# LC_Agregation_Boards.net
KiCad netlist of a schematic drawn in Altium Designer
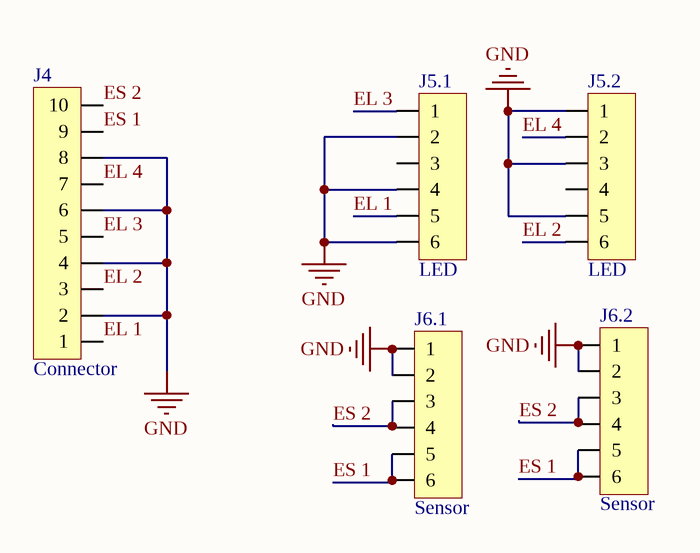
[diagram p0: LC Agregation Boards.SchDoc]

(export (version "E")
  (design (tool "Eeschema 10.0.6"))
  (components
    (comp (ref "J4")
      (value "Connector")
      (footprint "Connector:LINE 2.54 x 10D (2 x 5) - BH")
      (description "Vert, Dbl line, Male")
      (libsource (lib "Connector") (part "PLD-10 (2 x 5)"))
    )
    (comp (ref "J5.1")
      (value "LED")
      (footprint "Connector:LINE 2.54 x 6D (2 x 3)")
      (description "Vert, Dbl line, Male")
      (libsource (lib "Connector") (part "PLD-6 (2 x 3)"))
    )
    (comp (ref "J5.2")
      (value "LED")
      (footprint "Connector:LINE 2.54 x 6D (2 x 3)")
      (description "Vert, Dbl line, Male")
      (libsource (lib "Connector") (part "PLD-6 (2 x 3)"))
    )
    (comp (ref "J6.1")
      (value "Sensor")
      (footprint "Connector:LINE 2.54 x 6D (2 x 3)")
      (description "Vert, Dbl line, Male")
      (libsource (lib "Connector") (part "PLD-6 (2 x 3)"))
    )
    (comp (ref "J6.2")
      (value "Sensor")
      (footprint "Connector:LINE 2.54 x 6D (2 x 3)")
      (description "Vert, Dbl line, Male")
      (libsource (lib "Connector") (part "PLD-6 (2 x 3)"))
    )
  )
  (nets
    (net (code "1") (name "/EL 1") (class "Default")
      (node (ref "J4") (pin "1") (pinfunction "1_1") (pintype "passive"))
      (node (ref "J5.1") (pin "5") (pinfunction "5_5") (pintype "passive"))
    )
    (net (code "2") (name "/EL 2") (class "Default")
      (node (ref "J4") (pin "3") (pinfunction "3_3") (pintype "passive"))
      (node (ref "J5.2") (pin "6") (pinfunction "6_6") (pintype "passive"))
    )
    (net (code "3") (name "/EL 3") (class "Default")
      (node (ref "J4") (pin "5") (pinfunction "5_5") (pintype "passive"))
      (node (ref "J5.1") (pin "1") (pinfunction "1_1") (pintype "passive"))
    )
    (net (code "4") (name "/EL 4") (class "Default")
      (node (ref "J4") (pin "7") (pinfunction "7_7") (pintype "passive"))
      (node (ref "J5.2") (pin "2") (pinfunction "2_2") (pintype "passive"))
    )
    (net (code "5") (name "/ES 1") (class "Default")
      (node (ref "J4") (pin "9") (pinfunction "9_9") (pintype "passive"))
      (node (ref "J6.1") (pin "5") (pinfunction "5_5") (pintype "passive"))
      (node (ref "J6.1") (pin "6") (pinfunction "6_6") (pintype "passive"))
      (node (ref "J6.2") (pin "5") (pinfunction "5_5") (pintype "passive"))
      (node (ref "J6.2") (pin "6") (pinfunction "6_6") (pintype "passive"))
    )
    (net (code "6") (name "/ES 2") (class "Default")
      (node (ref "J4") (pin "10") (pinfunction "10_10") (pintype "passive"))
      (node (ref "J6.1") (pin "3") (pinfunction "3_3") (pintype "passive"))
      (node (ref "J6.1") (pin "4") (pinfunction "4_4") (pintype "passive"))
      (node (ref "J6.2") (pin "3") (pinfunction "3_3") (pintype "passive"))
      (node (ref "J6.2") (pin "4") (pinfunction "4_4") (pintype "passive"))
    )
    (net (code "7") (name "GND") (class "Default")
      (node (ref "J4") (pin "2") (pinfunction "2_2") (pintype "passive"))
      (node (ref "J4") (pin "4") (pinfunction "4_4") (pintype "passive"))
      (node (ref "J4") (pin "6") (pinfunction "6_6") (pintype "passive"))
      (node (ref "J4") (pin "8") (pinfunction "8_8") (pintype "passive"))
      (node (ref "J5.1") (pin "2") (pinfunction "2_2") (pintype "passive"))
      (node (ref "J5.1") (pin "4") (pinfunction "4_4") (pintype "passive"))
      (node (ref "J5.1") (pin "6") (pinfunction "6_6") (pintype "passive"))
      (node (ref "J5.2") (pin "1") (pinfunction "1_1") (pintype "passive"))
      (node (ref "J5.2") (pin "3") (pinfunction "3_3") (pintype "passive"))
      (node (ref "J5.2") (pin "5") (pinfunction "5_5") (pintype "passive"))
      (node (ref "J6.1") (pin "1") (pinfunction "1_1") (pintype "passive"))
      (node (ref "J6.1") (pin "2") (pinfunction "2_2") (pintype "passive"))
      (node (ref "J6.2") (pin "1") (pinfunction "1_1") (pintype "passive"))
      (node (ref "J6.2") (pin "2") (pinfunction "2_2") (pintype "passive"))
    )
    (net (code "8") (name "unconnected-(J5.1-Pad3)") (class "Default")
      (node (ref "J5.1") (pin "3") (pinfunction "3_3") (pintype "passive"))
    )
    (net (code "9") (name "unconnected-(J5.2-Pad4)") (class "Default")
      (node (ref "J5.2") (pin "4") (pinfunction "4_4") (pintype "passive"))
    )
  )
)
